# ESP32.net
KiCad netlist of a schematic drawn in Altium Designer
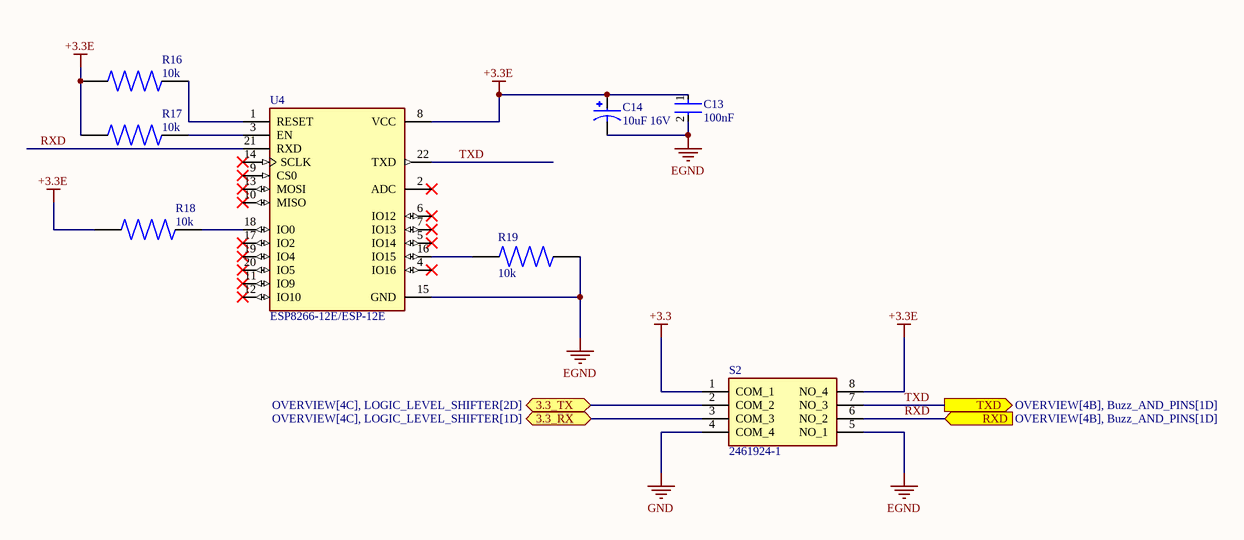
[diagram p0: ESP32.SchDoc]

(export (version "E")
  (design (tool "Eeschema 10.0.6"))
  (components
    (comp (ref "C13")
      (value "100nF")
      (footprint "FP-GRT31C-0_2-MFG")
      (description "Multi-Layer Ceramic Capacitor 100nF 50V C0G ±1% 1206 Emboss T/R")
      (libsource (lib "Altium Content Vault") (part "02cd4be3c70576c341d710602a673aa"))
    )
    (comp (ref "C14")
      (value "10uF 16V")
      (footprint "CAP_EEEHB1C100AR")
      (description "10ÂµF 16V Aluminum Electrolytic Capacitors Radial, Can - SMD 2000 Hrs @ 105Â°C")
      (fields (field (name "MP") "EEE-HB1C100AR") (field (name "MF") "Panasonic"))
      (libsource (lib "RFID") (part "EEEHB1C100AR"))
    )
    (comp (ref "R16")
      (value "10k")
      (footprint "RESC3115X65N")
      (description "Res Thick Film 1206 4.7K Ohm 1% 0.25W(1/4W) Â±100ppm/C Pad SMD T/R")
      (fields (field (name "MF") "TE Connectivity") (field (name "MP") "CRG1206F4K7/10"))
      (libsource (lib "RFID") (part "CRG1206F4K7/10"))
    )
    (comp (ref "R17")
      (value "10k")
      (footprint "RESC3115X65N")
      (description "Res Thick Film 1206 4.7K Ohm 1% 0.25W(1/4W) Â±100ppm/C Pad SMD T/R")
      (fields (field (name "MF") "TE Connectivity") (field (name "MP") "CRG1206F4K7/10"))
      (libsource (lib "RFID") (part "CRG1206F4K7/10"))
    )
    (comp (ref "R18")
      (value "10k")
      (footprint "RESC3115X65N")
      (description "Res Thick Film 1206 4.7K Ohm 1% 0.25W(1/4W) Â±100ppm/C Pad SMD T/R")
      (fields (field (name "MF") "TE Connectivity") (field (name "MP") "CRG1206F4K7/10"))
      (libsource (lib "RFID") (part "CRG1206F4K7/10"))
    )
    (comp (ref "R19")
      (value "10k")
      (footprint "RESC3115X65N")
      (description "Res Thick Film 1206 4.7K Ohm 1% 0.25W(1/4W) Â±100ppm/C Pad SMD T/R")
      (fields (field (name "MF") "TE Connectivity") (field (name "MP") "CRG1206F4K7/10"))
      (libsource (lib "RFID") (part "CRG1206F4K7/10"))
    )
    (comp (ref "S2")
      (value "2461924-1")
      (footprint "24619241")
      (description "Switch")
      (fields (field (name "MOUSER PART NUMBER") "655-2461924-1"))
      (libsource (lib "RFID") (part "2461924-1"))
    )
    (comp (ref "U4")
      (value "ESP8266-12E/ESP-12E")
      (footprint "XCVR_ESP8266-12E/ESP-12E")
      (fields (field (name "MF") "AI-Thinker"))
      (libsource (lib "RFID") (part "ESP8266-12E/ESP-12E"))
    )
  )
  (nets
    (net (code "1") (name "+3.3") (class "Default")
      (node (ref "S2") (pin "1") (pinfunction "COM_1_1") (pintype "passive"))
    )
    (net (code "2") (name "+3.3E") (class "Default")
      (node (ref "C13") (pin "1") (pinfunction "1_1") (pintype "passive"))
      (node (ref "C14") (pin "1") (pinfunction "1_1") (pintype "passive"))
      (node (ref "R16") (pin "1") (pinfunction "1_1") (pintype "passive"))
      (node (ref "R17") (pin "1") (pinfunction "1_1") (pintype "passive"))
      (node (ref "R18") (pin "1") (pinfunction "1_1") (pintype "passive"))
      (node (ref "S2") (pin "8") (pinfunction "NO_4_8") (pintype "passive"))
      (node (ref "U4") (pin "8") (pinfunction "VCC_8") (pintype "power_in"))
    )
    (net (code "3") (name "/3.3_RX") (class "Default")
      (node (ref "S2") (pin "3") (pinfunction "COM_3_3") (pintype "passive"))
    )
    (net (code "4") (name "/3.3_TX") (class "Default")
      (node (ref "S2") (pin "2") (pinfunction "COM_2_2") (pintype "passive"))
    )
    (net (code "5") (name "/RXD") (class "Default")
      (node (ref "S2") (pin "6") (pinfunction "NO_2_6") (pintype "passive"))
      (node (ref "U4") (pin "21") (pinfunction "RXD_21") (pintype "passive"))
    )
    (net (code "6") (name "/TXD") (class "Default")
      (node (ref "S2") (pin "7") (pinfunction "NO_3_7") (pintype "passive"))
      (node (ref "U4") (pin "22") (pinfunction "TXD_22") (pintype "output"))
    )
    (net (code "7") (name "EGND") (class "Default")
      (node (ref "C13") (pin "2") (pinfunction "2_2") (pintype "passive"))
      (node (ref "C14") (pin "2") (pinfunction "2_2") (pintype "passive"))
      (node (ref "R19") (pin "2") (pinfunction "2_2") (pintype "passive"))
      (node (ref "S2") (pin "5") (pinfunction "NO_1_5") (pintype "passive"))
      (node (ref "U4") (pin "15") (pinfunction "GND_15") (pintype "power_in"))
    )
    (net (code "8") (name "GND") (class "Default")
      (node (ref "S2") (pin "4") (pinfunction "COM_4_4") (pintype "passive"))
    )
    (net (code "9") (name "Net-(U4-EN)") (class "Default")
      (node (ref "R17") (pin "2") (pinfunction "2_2") (pintype "passive"))
      (node (ref "U4") (pin "3") (pinfunction "EN_3") (pintype "passive"))
    )
    (net (code "10") (name "Net-(U4-IO0)") (class "Default")
      (node (ref "R18") (pin "2") (pinfunction "2_2") (pintype "passive"))
      (node (ref "U4") (pin "18") (pinfunction "IO0_18") (pintype "bidirectional"))
    )
    (net (code "11") (name "Net-(U4-IO15)") (class "Default")
      (node (ref "R19") (pin "1") (pinfunction "1_1") (pintype "passive"))
      (node (ref "U4") (pin "16") (pinfunction "IO15_16") (pintype "bidirectional"))
    )
    (net (code "12") (name "Net-(U4-RESET)") (class "Default")
      (node (ref "R16") (pin "2") (pinfunction "2_2") (pintype "passive"))
      (node (ref "U4") (pin "1") (pinfunction "RESET_1") (pintype "passive"))
    )
    (net (code "13") (name "unconnected-(U4-ADC-Pad2)") (class "Default")
      (node (ref "U4") (pin "2") (pinfunction "ADC_2") (pintype "passive+no_connect"))
    )
    (net (code "14") (name "unconnected-(U4-CS0-Pad9)") (class "Default")
      (node (ref "U4") (pin "9") (pinfunction "CS0_9") (pintype "input+no_connect"))
    )
    (net (code "15") (name "unconnected-(U4-IO2-Pad17)") (class "Default")
      (node (ref "U4") (pin "17") (pinfunction "IO2_17") (pintype "bidirectional+no_connect"))
    )
    (net (code "16") (name "unconnected-(U4-IO4-Pad19)") (class "Default")
      (node (ref "U4") (pin "19") (pinfunction "IO4_19") (pintype "bidirectional+no_connect"))
    )
    (net (code "17") (name "unconnected-(U4-IO5-Pad20)") (class "Default")
      (node (ref "U4") (pin "20") (pinfunction "IO5_20") (pintype "bidirectional+no_connect"))
    )
    (net (code "18") (name "unconnected-(U4-IO9-Pad11)") (class "Default")
      (node (ref "U4") (pin "11") (pinfunction "IO9_11") (pintype "bidirectional+no_connect"))
    )
    (net (code "19") (name "unconnected-(U4-IO10-Pad12)") (class "Default")
      (node (ref "U4") (pin "12") (pinfunction "IO10_12") (pintype "bidirectional+no_connect"))
    )
    (net (code "20") (name "unconnected-(U4-IO12-Pad6)") (class "Default")
      (node (ref "U4") (pin "6") (pinfunction "IO12_6") (pintype "bidirectional+no_connect"))
    )
    (net (code "21") (name "unconnected-(U4-IO13-Pad7)") (class "Default")
      (node (ref "U4") (pin "7") (pinfunction "IO13_7") (pintype "bidirectional+no_connect"))
    )
    (net (code "22") (name "unconnected-(U4-IO14-Pad5)") (class "Default")
      (node (ref "U4") (pin "5") (pinfunction "IO14_5") (pintype "bidirectional+no_connect"))
    )
    (net (code "23") (name "unconnected-(U4-IO16-Pad4)") (class "Default")
      (node (ref "U4") (pin "4") (pinfunction "IO16_4") (pintype "bidirectional+no_connect"))
    )
    (net (code "24") (name "unconnected-(U4-MISO-Pad10)") (class "Default")
      (node (ref "U4") (pin "10") (pinfunction "MISO_10") (pintype "bidirectional+no_connect"))
    )
    (net (code "25") (name "unconnected-(U4-MOSI-Pad13)") (class "Default")
      (node (ref "U4") (pin "13") (pinfunction "MOSI_13") (pintype "bidirectional+no_connect"))
    )
    (net (code "26") (name "unconnected-(U4-SCLK-Pad14)") (class "Default")
      (node (ref "U4") (pin "14") (pinfunction "SCLK_14") (pintype "input+no_connect"))
    )
  )
)
